# BlinkyTile_Controller.net
KiCad netlist of a schematic drawn in EAGLE
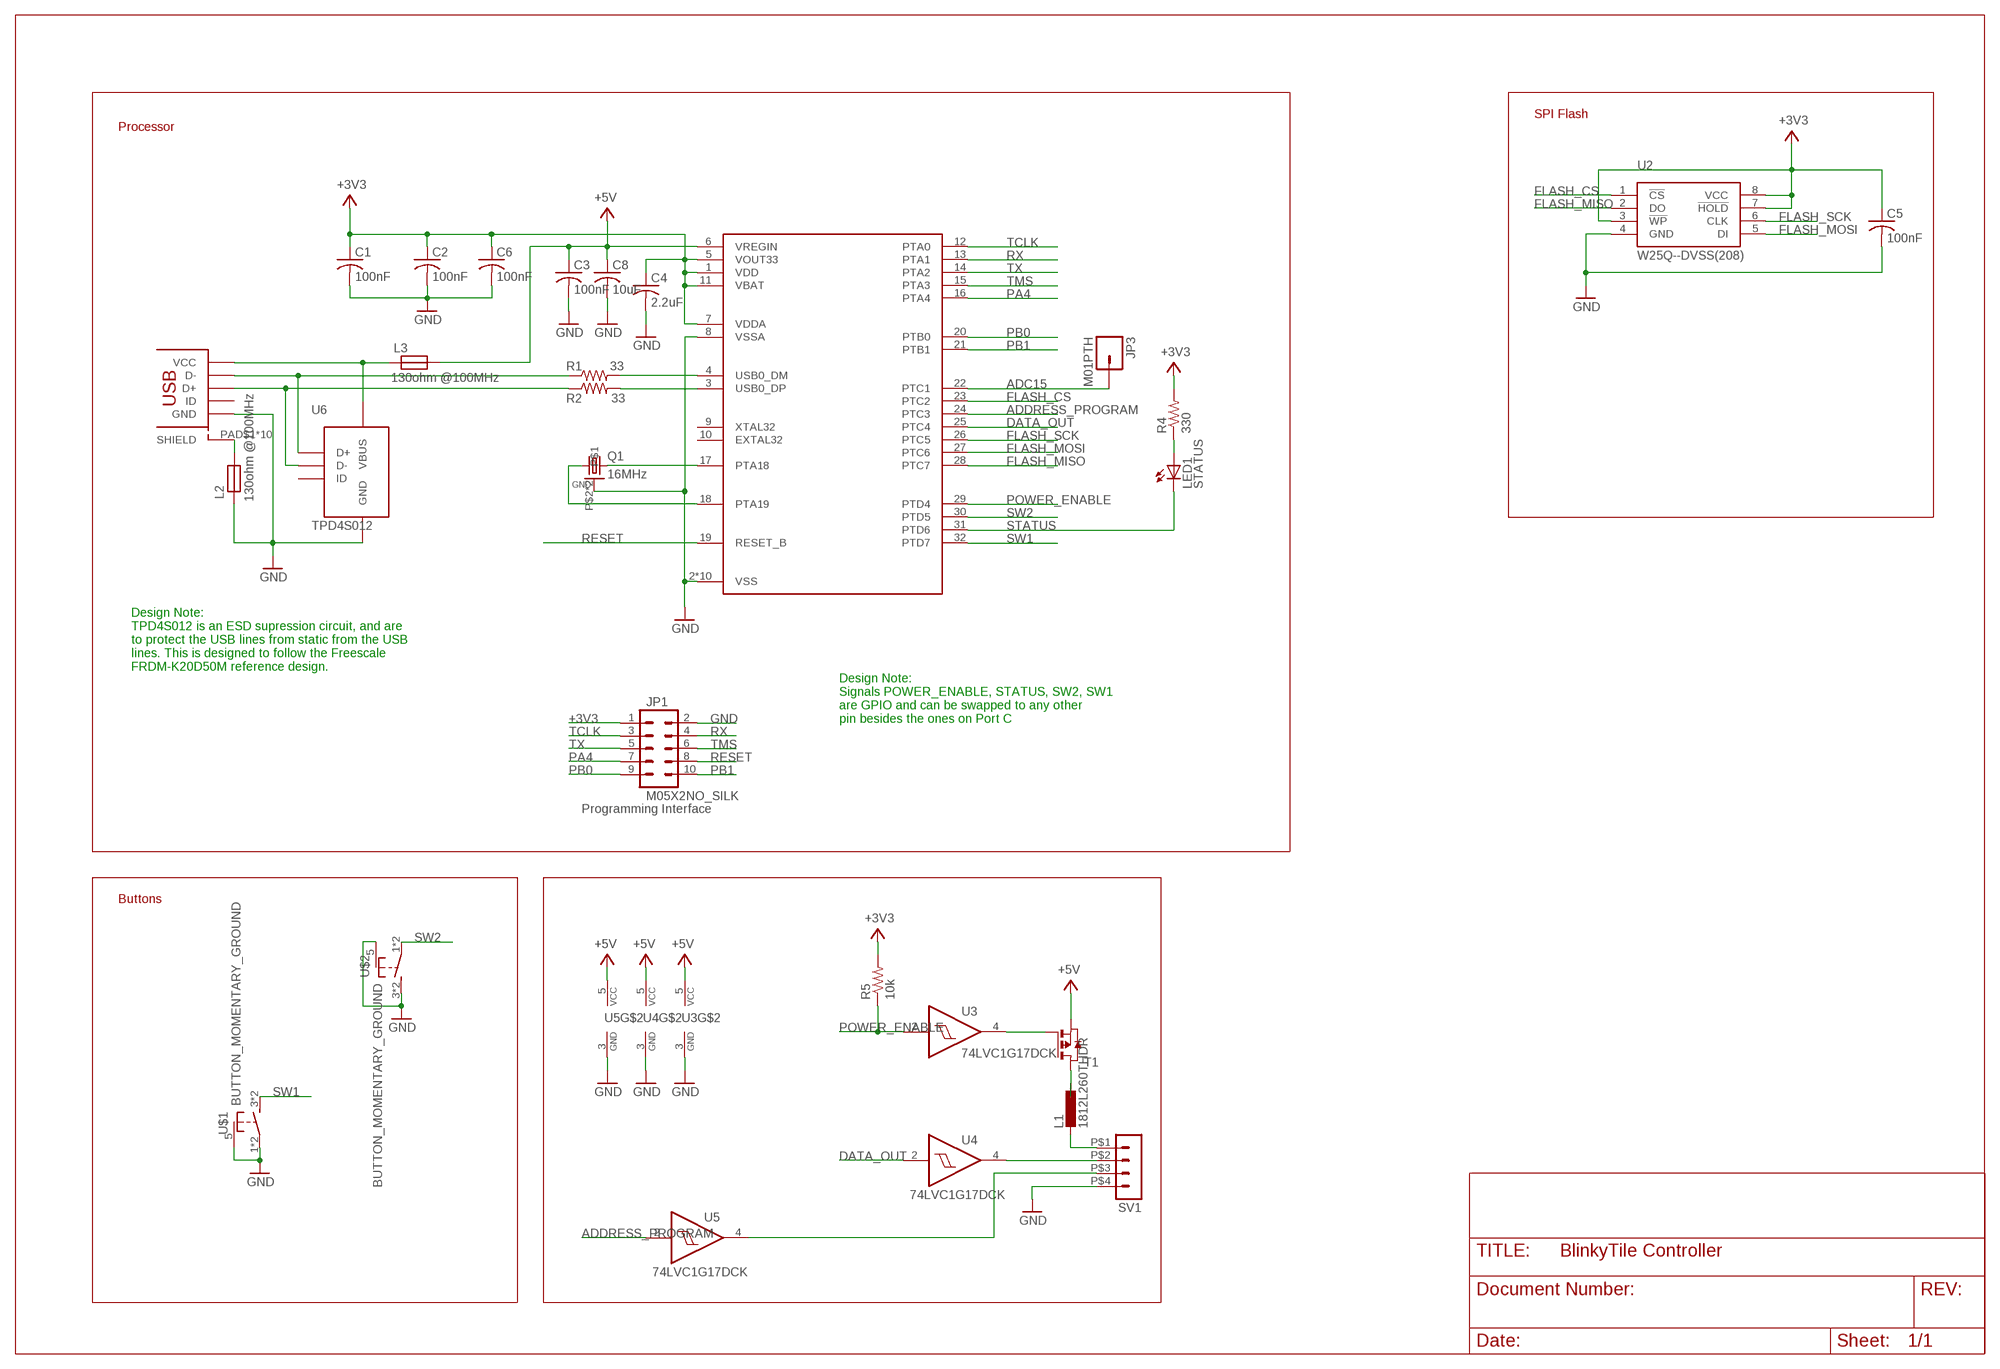
[diagram p0: schematic, sheet 1]

(export (version "E")
  (design (tool "Eeschema 10.0.6"))
  (components
    (comp (ref "C1")
      (value "100nF")
      (footprint "eagle-import:C0402")
      (libsource (lib "eagle-import") (part "C-USC0402"))
    )
    (comp (ref "C2")
      (value "100nF")
      (footprint "eagle-import:C0402")
      (libsource (lib "eagle-import") (part "C-USC0402"))
    )
    (comp (ref "C3")
      (value "100nF")
      (footprint "eagle-import:C0402")
      (libsource (lib "eagle-import") (part "C-USC0402"))
    )
    (comp (ref "C4")
      (value "2.2uF")
      (footprint "eagle-import:C0402")
      (libsource (lib "eagle-import") (part "C-USC0402"))
    )
    (comp (ref "C5")
      (value "100nF")
      (footprint "eagle-import:C0402")
      (libsource (lib "eagle-import") (part "C-USC0402"))
    )
    (comp (ref "C6")
      (value "100nF")
      (footprint "eagle-import:C0402")
      (libsource (lib "eagle-import") (part "C-USC0402"))
    )
    (comp (ref "C8")
      (value "10uF")
      (footprint "eagle-import:C0805K")
      (libsource (lib "eagle-import") (part "C-USC0805K"))
    )
    (comp (ref "CON1")
      (value "USB_MICROSMT+THRUHULE")
      (footprint "eagle-import:USB_MICRO_THRUHOLE")
      (libsource (lib "eagle-import") (part "USB_MICROSMT+THRUHULE"))
    )
    (comp (ref "JP1")
      (value "M05X2NO_SILK")
      (footprint "eagle-import:2X5_NOSILK")
      (libsource (lib "eagle-import") (part "M05X2NO_SILK"))
    )
    (comp (ref "JP3")
      (value "M01PTH")
      (footprint "eagle-import:1X01")
      (libsource (lib "eagle-import") (part "M01PTH"))
    )
    (comp (ref "L1")
      (value "1812L260THDR")
      (footprint "eagle-import:L1812")
      (libsource (lib "eagle-import") (part "L-EUL1812"))
    )
    (comp (ref "L2")
      (value "130ohm @100MHz")
      (footprint "eagle-import:0805")
      (libsource (lib "eagle-import") (part "FB0805/NO-OUTLINE"))
    )
    (comp (ref "L3")
      (value "130ohm @100MHz")
      (footprint "eagle-import:0805")
      (libsource (lib "eagle-import") (part "FB0805/NO-OUTLINE"))
    )
    (comp (ref "LED1")
      (value "STATUS")
      (footprint "eagle-import:CHIPLED_0805")
      (libsource (lib "eagle-import") (part "LEDCHIPLED_0805"))
    )
    (comp (ref "Q1")
      (value "16MHz")
      (footprint "eagle-import:CRSYTAL_2520")
      (libsource (lib "eagle-import") (part "CRYSTAL_4PAD2520"))
    )
    (comp (ref "R1")
      (value "33")
      (footprint "eagle-import:R0402")
      (libsource (lib "eagle-import") (part "R-US_R0402"))
    )
    (comp (ref "R2")
      (value "33")
      (footprint "eagle-import:R0402")
      (libsource (lib "eagle-import") (part "R-US_R0402"))
    )
    (comp (ref "R4")
      (value "330")
      (footprint "eagle-import:R0402")
      (libsource (lib "eagle-import") (part "R-US_R0402"))
    )
    (comp (ref "R5")
      (value "10k")
      (footprint "eagle-import:R0402")
      (libsource (lib "eagle-import") (part "R-US_R0402"))
    )
    (comp (ref "SV1")
      (value "4-PIN_DUPONT")
      (footprint "eagle-import:DUPONT-4P")
      (libsource (lib "eagle-import") (part "4-PIN_DUPONT"))
    )
    (comp (ref "T1")
      (value "PMOSSOT23")
      (footprint "eagle-import:SOT-23")
      (libsource (lib "eagle-import") (part "PMOSSOT23"))
    )
    (comp (ref "U$1")
      (value "BUTTON_MOMENTARY_GROUND")
      (footprint "eagle-import:TD-07XB")
      (libsource (lib "eagle-import") (part "BUTTON_MOMENTARY_GROUND"))
    )
    (comp (ref "U$2")
      (value "BUTTON_MOMENTARY_GROUND")
      (footprint "eagle-import:TD-07XB")
      (libsource (lib "eagle-import") (part "BUTTON_MOMENTARY_GROUND"))
    )
    (comp (ref "U1")
      (value "MK20D--VFM5")
      (footprint "eagle-import:QFN32_5X5_LONGLEADS")
      (libsource (lib "eagle-import") (part "MK20D--VFM5"))
    )
    (comp (ref "U2")
      (value "W25Q--DVSS(208)")
      (footprint "eagle-import:SOIC8-208")
      (libsource (lib "eagle-import") (part "W25Q--DVSS(208)"))
    )
    (comp (ref "U3")
      (value "74LVC1G17DCK")
      (footprint "eagle-import:SC70-5")
      (libsource (lib "eagle-import") (part "741G17DCKLVC"))
    )
    (comp (ref "U4")
      (value "74LVC1G17DCK")
      (footprint "eagle-import:SC70-5")
      (libsource (lib "eagle-import") (part "741G17DCKLVC"))
    )
    (comp (ref "U5")
      (value "74LVC1G17DCK")
      (footprint "eagle-import:SC70-5")
      (libsource (lib "eagle-import") (part "741G17DCKLVC"))
    )
    (comp (ref "U6")
      (value "TPD4S012")
      (footprint "eagle-import:R-PUSON-N6")
      (libsource (lib "eagle-import") (part "TPD4S012"))
    )
  )
  (nets
    (net (code "1") (name "+3V3") (class "Default")
      (node (ref "C1") (pin "1") (pinfunction "1_1") (pintype "passive"))
      (node (ref "C2") (pin "1") (pinfunction "1_1") (pintype "passive"))
      (node (ref "C4") (pin "1") (pinfunction "1_1") (pintype "passive"))
      (node (ref "C5") (pin "1") (pinfunction "1_1") (pintype "passive"))
      (node (ref "C6") (pin "1") (pinfunction "1_1") (pintype "passive"))
      (node (ref "JP1") (pin "1") (pinfunction "1_1") (pintype "passive"))
      (node (ref "R4") (pin "2") (pinfunction "2_2") (pintype "passive"))
      (node (ref "R5") (pin "2") (pinfunction "2_2") (pintype "passive"))
      (node (ref "U1") (pin "1") (pinfunction "VDD_1") (pintype "bidirectional"))
      (node (ref "U1") (pin "11") (pinfunction "VBAT_11") (pintype "bidirectional"))
      (node (ref "U1") (pin "5") (pinfunction "VOUT33_5") (pintype "bidirectional"))
      (node (ref "U1") (pin "7") (pinfunction "VDDA_7") (pintype "bidirectional"))
      (node (ref "U2") (pin "3") (pinfunction "~{WP}_3") (pintype "bidirectional"))
      (node (ref "U2") (pin "7") (pinfunction "~{HOLD}_7") (pintype "bidirectional"))
      (node (ref "U2") (pin "8") (pinfunction "VCC_8") (pintype "bidirectional"))
    )
    (net (code "2") (name "+5V") (class "Default")
      (node (ref "C3") (pin "1") (pinfunction "1_1") (pintype "passive"))
      (node (ref "C8") (pin "1") (pinfunction "1_1") (pintype "passive"))
      (node (ref "L3") (pin "1") (pinfunction "P$1_1") (pintype "bidirectional"))
      (node (ref "T1") (pin "2") (pinfunction "S_2") (pintype "passive"))
      (node (ref "U1") (pin "6") (pinfunction "VREGIN_6") (pintype "bidirectional"))
      (node (ref "U3") (pin "5") (pinfunction "VCC_5") (pintype "power_in"))
      (node (ref "U4") (pin "5") (pinfunction "VCC_5") (pintype "power_in"))
      (node (ref "U5") (pin "5") (pinfunction "VCC_5") (pintype "power_in"))
    )
    (net (code "3") (name "/ADC15") (class "Default")
      (node (ref "JP3") (pin "1") (pinfunction "1_1") (pintype "passive"))
      (node (ref "U1") (pin "22") (pinfunction "PTC1_22") (pintype "bidirectional"))
    )
    (net (code "4") (name "/ADDRESS_PROGRAM") (class "Default")
      (node (ref "U1") (pin "24") (pinfunction "PTC3_24") (pintype "bidirectional"))
      (node (ref "U5") (pin "2") (pinfunction "I_2") (pintype "input"))
    )
    (net (code "5") (name "/DATA_OUT") (class "Default")
      (node (ref "U1") (pin "25") (pinfunction "PTC4_25") (pintype "bidirectional"))
      (node (ref "U4") (pin "2") (pinfunction "I_2") (pintype "input"))
    )
    (net (code "6") (name "/FLASH_CS") (class "Default")
      (node (ref "U1") (pin "23") (pinfunction "PTC2_23") (pintype "bidirectional"))
      (node (ref "U2") (pin "1") (pinfunction "~{CS}_1") (pintype "bidirectional"))
    )
    (net (code "7") (name "/FLASH_MISO") (class "Default")
      (node (ref "U1") (pin "28") (pinfunction "PTC7_28") (pintype "bidirectional"))
      (node (ref "U2") (pin "2") (pinfunction "DO_2") (pintype "bidirectional"))
    )
    (net (code "8") (name "/FLASH_MOSI") (class "Default")
      (node (ref "U1") (pin "27") (pinfunction "PTC6_27") (pintype "bidirectional"))
      (node (ref "U2") (pin "5") (pinfunction "DI_5") (pintype "bidirectional"))
    )
    (net (code "9") (name "/FLASH_SCK") (class "Default")
      (node (ref "U1") (pin "26") (pinfunction "PTC5_26") (pintype "bidirectional"))
      (node (ref "U2") (pin "6") (pinfunction "CLK_6") (pintype "bidirectional"))
    )
    (net (code "10") (name "/PA4") (class "Default")
      (node (ref "JP1") (pin "7") (pinfunction "7_7") (pintype "passive"))
      (node (ref "U1") (pin "16") (pinfunction "PTA4_16") (pintype "bidirectional"))
    )
    (net (code "11") (name "/PB0") (class "Default")
      (node (ref "JP1") (pin "9") (pinfunction "9_9") (pintype "passive"))
      (node (ref "U1") (pin "20") (pinfunction "PTB0_20") (pintype "bidirectional"))
    )
    (net (code "12") (name "/PB1") (class "Default")
      (node (ref "JP1") (pin "10") (pinfunction "10_10") (pintype "passive"))
      (node (ref "U1") (pin "21") (pinfunction "PTB1_21") (pintype "bidirectional"))
    )
    (net (code "13") (name "/POWER_ENABLE") (class "Default")
      (node (ref "R5") (pin "1") (pinfunction "1_1") (pintype "passive"))
      (node (ref "U1") (pin "29") (pinfunction "PTD4_29") (pintype "bidirectional"))
      (node (ref "U3") (pin "2") (pinfunction "I_2") (pintype "input"))
    )
    (net (code "14") (name "/RESET") (class "Default")
      (node (ref "JP1") (pin "8") (pinfunction "8_8") (pintype "passive"))
      (node (ref "U1") (pin "19") (pinfunction "RESET_B_19") (pintype "bidirectional"))
    )
    (net (code "15") (name "/RX") (class "Default")
      (node (ref "JP1") (pin "4") (pinfunction "4_4") (pintype "passive"))
      (node (ref "U1") (pin "13") (pinfunction "PTA1_13") (pintype "bidirectional"))
    )
    (net (code "16") (name "/STATUS") (class "Default")
      (node (ref "LED1") (pin "C") (pinfunction "C_C") (pintype "passive"))
      (node (ref "U1") (pin "31") (pinfunction "PTD6_31") (pintype "bidirectional"))
    )
    (net (code "17") (name "/SW1") (class "Default")
      (node (ref "U$1") (pin "3") (pinfunction "S_3") (pintype "passive"))
      (node (ref "U$1") (pin "4") (pinfunction "S_4") (pintype "passive"))
      (node (ref "U1") (pin "32") (pinfunction "PTD7_32") (pintype "bidirectional"))
    )
    (net (code "18") (name "/SW2") (class "Default")
      (node (ref "U$2") (pin "1") (pinfunction "P_1") (pintype "passive"))
      (node (ref "U$2") (pin "2") (pinfunction "P_2") (pintype "passive"))
      (node (ref "U1") (pin "30") (pinfunction "PTD5_30") (pintype "bidirectional"))
    )
    (net (code "19") (name "/TCLK") (class "Default")
      (node (ref "JP1") (pin "3") (pinfunction "3_3") (pintype "passive"))
      (node (ref "U1") (pin "12") (pinfunction "PTA0_12") (pintype "bidirectional"))
    )
    (net (code "20") (name "/TMS") (class "Default")
      (node (ref "JP1") (pin "6") (pinfunction "6_6") (pintype "passive"))
      (node (ref "U1") (pin "15") (pinfunction "PTA3_15") (pintype "bidirectional"))
    )
    (net (code "21") (name "/TX") (class "Default")
      (node (ref "JP1") (pin "5") (pinfunction "5_5") (pintype "passive"))
      (node (ref "U1") (pin "14") (pinfunction "PTA2_14") (pintype "bidirectional"))
    )
    (net (code "22") (name "GND") (class "Default")
      (node (ref "C1") (pin "2") (pinfunction "2_2") (pintype "passive"))
      (node (ref "C2") (pin "2") (pinfunction "2_2") (pintype "passive"))
      (node (ref "C3") (pin "2") (pinfunction "2_2") (pintype "passive"))
      (node (ref "C4") (pin "2") (pinfunction "2_2") (pintype "passive"))
      (node (ref "C5") (pin "2") (pinfunction "2_2") (pintype "passive"))
      (node (ref "C6") (pin "2") (pinfunction "2_2") (pintype "passive"))
      (node (ref "C8") (pin "2") (pinfunction "2_2") (pintype "passive"))
      (node (ref "CON1") (pin "PIN$5") (pinfunction "GND_PIN$5") (pintype "bidirectional"))
      (node (ref "JP1") (pin "2") (pinfunction "2_2") (pintype "passive"))
      (node (ref "L2") (pin "2") (pinfunction "P$2_2") (pintype "bidirectional"))
      (node (ref "Q1") (pin "P$2") (pinfunction "P$1_P$2") (pintype "bidirectional"))
      (node (ref "Q1") (pin "P$4") (pinfunction "P$1_P$4") (pintype "bidirectional"))
      (node (ref "SV1") (pin "P$4") (pinfunction "4_P$4") (pintype "passive"))
      (node (ref "U$1") (pin "1") (pinfunction "P_1") (pintype "passive"))
      (node (ref "U$1") (pin "2") (pinfunction "P_2") (pintype "passive"))
      (node (ref "U$1") (pin "5") (pinfunction "SHIELD_5") (pintype "passive"))
      (node (ref "U$2") (pin "3") (pinfunction "S_3") (pintype "passive"))
      (node (ref "U$2") (pin "4") (pinfunction "S_4") (pintype "passive"))
      (node (ref "U$2") (pin "5") (pinfunction "SHIELD_5") (pintype "passive"))
      (node (ref "U1") (pin "2") (pinfunction "VSS_2") (pintype "bidirectional"))
      (node (ref "U1") (pin "8") (pinfunction "VSSA_8") (pintype "bidirectional"))
      (node (ref "U1") (pin "PAD@1") (pinfunction "VSS_PAD@1") (pintype "bidirectional"))
      (node (ref "U1") (pin "PAD@10") (pinfunction "VSS_PAD@10") (pintype "bidirectional"))
      (node (ref "U1") (pin "PAD@11") (pinfunction "VSS_PAD@11") (pintype "bidirectional"))
      (node (ref "U1") (pin "PAD@2") (pinfunction "VSS_PAD@2") (pintype "bidirectional"))
      (node (ref "U1") (pin "PAD@3") (pinfunction "VSS_PAD@3") (pintype "bidirectional"))
      (node (ref "U1") (pin "PAD@4") (pinfunction "VSS_PAD@4") (pintype "bidirectional"))
      (node (ref "U1") (pin "PAD@5") (pinfunction "VSS_PAD@5") (pintype "bidirectional"))
      (node (ref "U1") (pin "PAD@6") (pinfunction "VSS_PAD@6") (pintype "bidirectional"))
      (node (ref "U1") (pin "PAD@9") (pinfunction "VSS_PAD@9") (pintype "bidirectional"))
      (node (ref "U2") (pin "4") (pinfunction "GND_4") (pintype "bidirectional"))
      (node (ref "U3") (pin "3") (pinfunction "GND_3") (pintype "power_in"))
      (node (ref "U4") (pin "3") (pinfunction "GND_3") (pintype "power_in"))
      (node (ref "U5") (pin "3") (pinfunction "GND_3") (pintype "power_in"))
      (node (ref "U6") (pin "P$4") (pinfunction "GND_P$4") (pintype "bidirectional"))
    )
    (net (code "23") (name "Net-(CON1-D+)") (class "Default")
      (node (ref "CON1") (pin "PIN$3") (pinfunction "D+_PIN$3") (pintype "bidirectional"))
      (node (ref "R2") (pin "1") (pinfunction "1_1") (pintype "passive"))
      (node (ref "U6") (pin "P$2") (pinfunction "D-_P$2") (pintype "bidirectional"))
    )
    (net (code "24") (name "Net-(CON1-D-)") (class "Default")
      (node (ref "CON1") (pin "PIN$2") (pinfunction "D-_PIN$2") (pintype "bidirectional"))
      (node (ref "R1") (pin "1") (pinfunction "1_1") (pintype "passive"))
      (node (ref "U6") (pin "P$1") (pinfunction "D+_P$1") (pintype "bidirectional"))
    )
    (net (code "25") (name "Net-(CON1-VCC)") (class "Default")
      (node (ref "CON1") (pin "PIN$1") (pinfunction "VCC_PIN$1") (pintype "bidirectional"))
      (node (ref "L3") (pin "2") (pinfunction "P$2_2") (pintype "bidirectional"))
      (node (ref "U6") (pin "P$6") (pinfunction "VBUS_P$6") (pintype "bidirectional"))
    )
    (net (code "26") (name "Net-(L2-P$1)") (class "Default")
      (node (ref "CON1") (pin "PAD$1") (pinfunction "SHIELD_PAD$1") (pintype "bidirectional"))
      (node (ref "CON1") (pin "PAD$10") (pinfunction "SHIELD_PAD$10") (pintype "bidirectional"))
      (node (ref "CON1") (pin "PAD$2") (pinfunction "SHIELD_PAD$2") (pintype "bidirectional"))
      (node (ref "CON1") (pin "PAD$3") (pinfunction "SHIELD_PAD$3") (pintype "bidirectional"))
      (node (ref "CON1") (pin "PAD$4") (pinfunction "SHIELD_PAD$4") (pintype "bidirectional"))
      (node (ref "CON1") (pin "PAD$5") (pinfunction "SHIELD_PAD$5") (pintype "bidirectional"))
      (node (ref "CON1") (pin "PAD$6") (pinfunction "SHIELD_PAD$6") (pintype "bidirectional"))
      (node (ref "CON1") (pin "PAD$7") (pinfunction "SHIELD_PAD$7") (pintype "bidirectional"))
      (node (ref "CON1") (pin "PAD$8") (pinfunction "SHIELD_PAD$8") (pintype "bidirectional"))
      (node (ref "CON1") (pin "PAD$9") (pinfunction "SHIELD_PAD$9") (pintype "bidirectional"))
      (node (ref "L2") (pin "1") (pinfunction "P$1_1") (pintype "bidirectional"))
    )
    (net (code "27") (name "Net-(LED1-PadA)") (class "Default")
      (node (ref "LED1") (pin "A") (pinfunction "A_A") (pintype "passive"))
      (node (ref "R4") (pin "1") (pinfunction "1_1") (pintype "passive"))
    )
    (net (code "28") (name "Net-(Q1-1)") (class "Default")
      (node (ref "Q1") (pin "P$1") (pinfunction "1_P$1") (pintype "passive"))
      (node (ref "U1") (pin "18") (pinfunction "PTA19_18") (pintype "bidirectional"))
    )
    (net (code "29") (name "Net-(Q1-2)") (class "Default")
      (node (ref "Q1") (pin "P$3") (pinfunction "2_P$3") (pintype "passive"))
      (node (ref "U1") (pin "17") (pinfunction "PTA18_17") (pintype "bidirectional"))
    )
    (net (code "30") (name "Net-(SV1-1)") (class "Default")
      (node (ref "L1") (pin "2") (pinfunction "2_2") (pintype "passive"))
      (node (ref "SV1") (pin "P$1") (pinfunction "1_P$1") (pintype "passive"))
    )
    (net (code "31") (name "Net-(SV1-2)") (class "Default")
      (node (ref "SV1") (pin "P$2") (pinfunction "2_P$2") (pintype "passive"))
      (node (ref "U4") (pin "4") (pinfunction "O_4") (pintype "output"))
    )
    (net (code "32") (name "Net-(SV1-3)") (class "Default")
      (node (ref "SV1") (pin "P$3") (pinfunction "3_P$3") (pintype "passive"))
      (node (ref "U5") (pin "4") (pinfunction "O_4") (pintype "output"))
    )
    (net (code "33") (name "Net-(T1-D)") (class "Default")
      (node (ref "L1") (pin "1") (pinfunction "1_1") (pintype "passive"))
      (node (ref "T1") (pin "1") (pinfunction "D_1") (pintype "passive"))
    )
    (net (code "34") (name "Net-(T1-G)") (class "Default")
      (node (ref "T1") (pin "3") (pinfunction "G_3") (pintype "passive"))
      (node (ref "U3") (pin "4") (pinfunction "O_4") (pintype "output"))
    )
    (net (code "35") (name "Net-(U1-USB0_DM)") (class "Default")
      (node (ref "R1") (pin "2") (pinfunction "2_2") (pintype "passive"))
      (node (ref "U1") (pin "4") (pinfunction "USB0_DM_4") (pintype "bidirectional"))
    )
    (net (code "36") (name "Net-(U1-USB0_DP)") (class "Default")
      (node (ref "R2") (pin "2") (pinfunction "2_2") (pintype "passive"))
      (node (ref "U1") (pin "3") (pinfunction "USB0_DP_3") (pintype "bidirectional"))
    )
    (net (code "37") (name "unconnected-(CON1-ID-PadPIN$4)") (class "Default")
      (node (ref "CON1") (pin "PIN$4") (pinfunction "ID_PIN$4") (pintype "bidirectional"))
    )
    (net (code "38") (name "unconnected-(U1-EXTAL32-Pad10)") (class "Default")
      (node (ref "U1") (pin "10") (pinfunction "EXTAL32_10") (pintype "bidirectional"))
    )
    (net (code "39") (name "unconnected-(U1-XTAL32-Pad9)") (class "Default")
      (node (ref "U1") (pin "9") (pinfunction "XTAL32_9") (pintype "bidirectional"))
    )
    (net (code "40") (name "unconnected-(U6-ID-PadP$3)") (class "Default")
      (node (ref "U6") (pin "P$3") (pinfunction "ID_P$3") (pintype "bidirectional"))
    )
  )
)
